# ExternalMotorControllerRev4.net
KiCad netlist of a schematic drawn in EAGLE
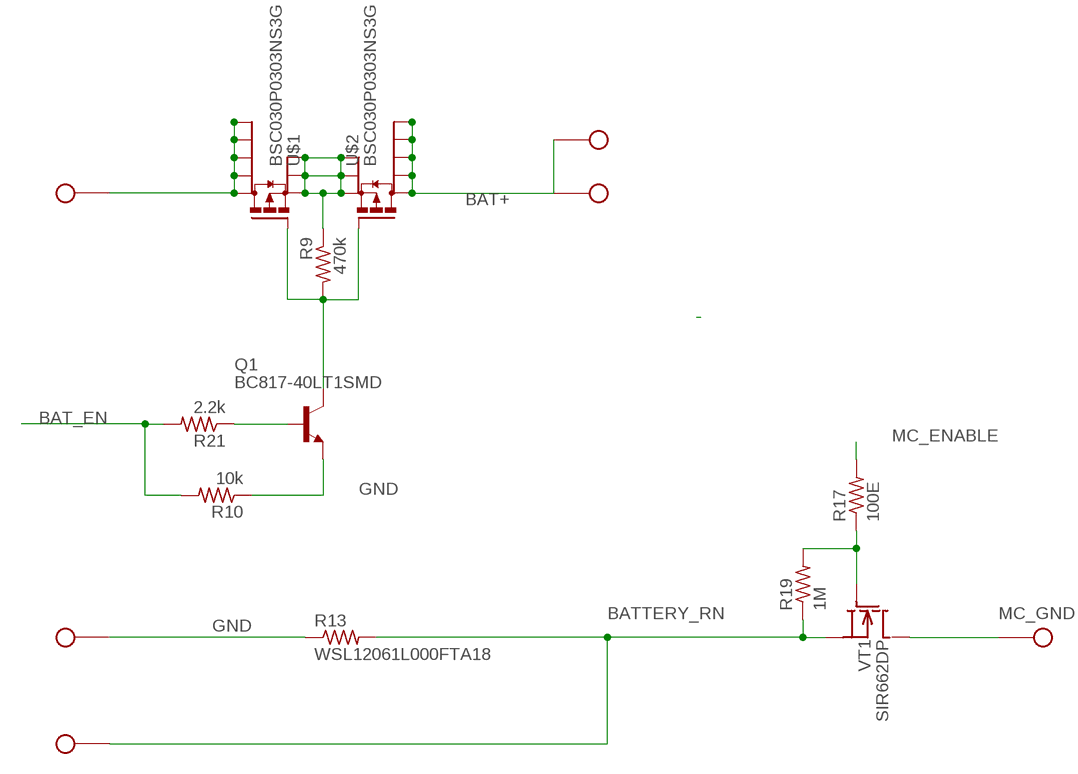
[diagram p0: schematic, sheet 1]
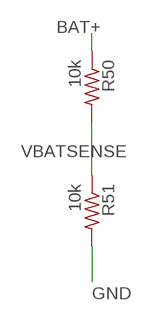
[diagram p1: schematic, sheet 3]
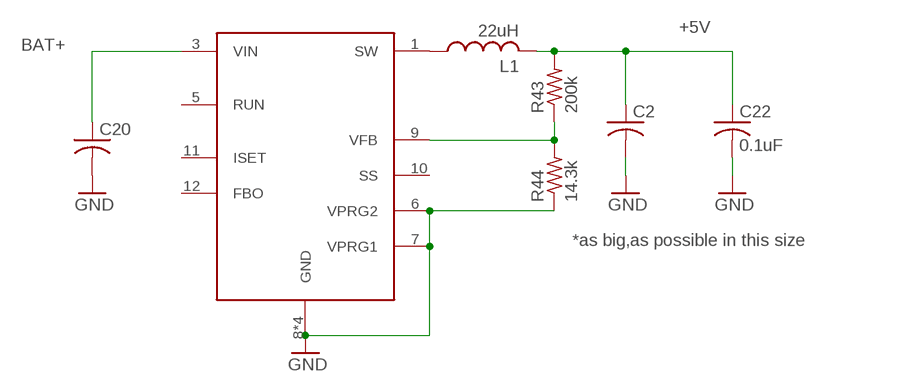
[diagram p2: schematic, sheet 4]
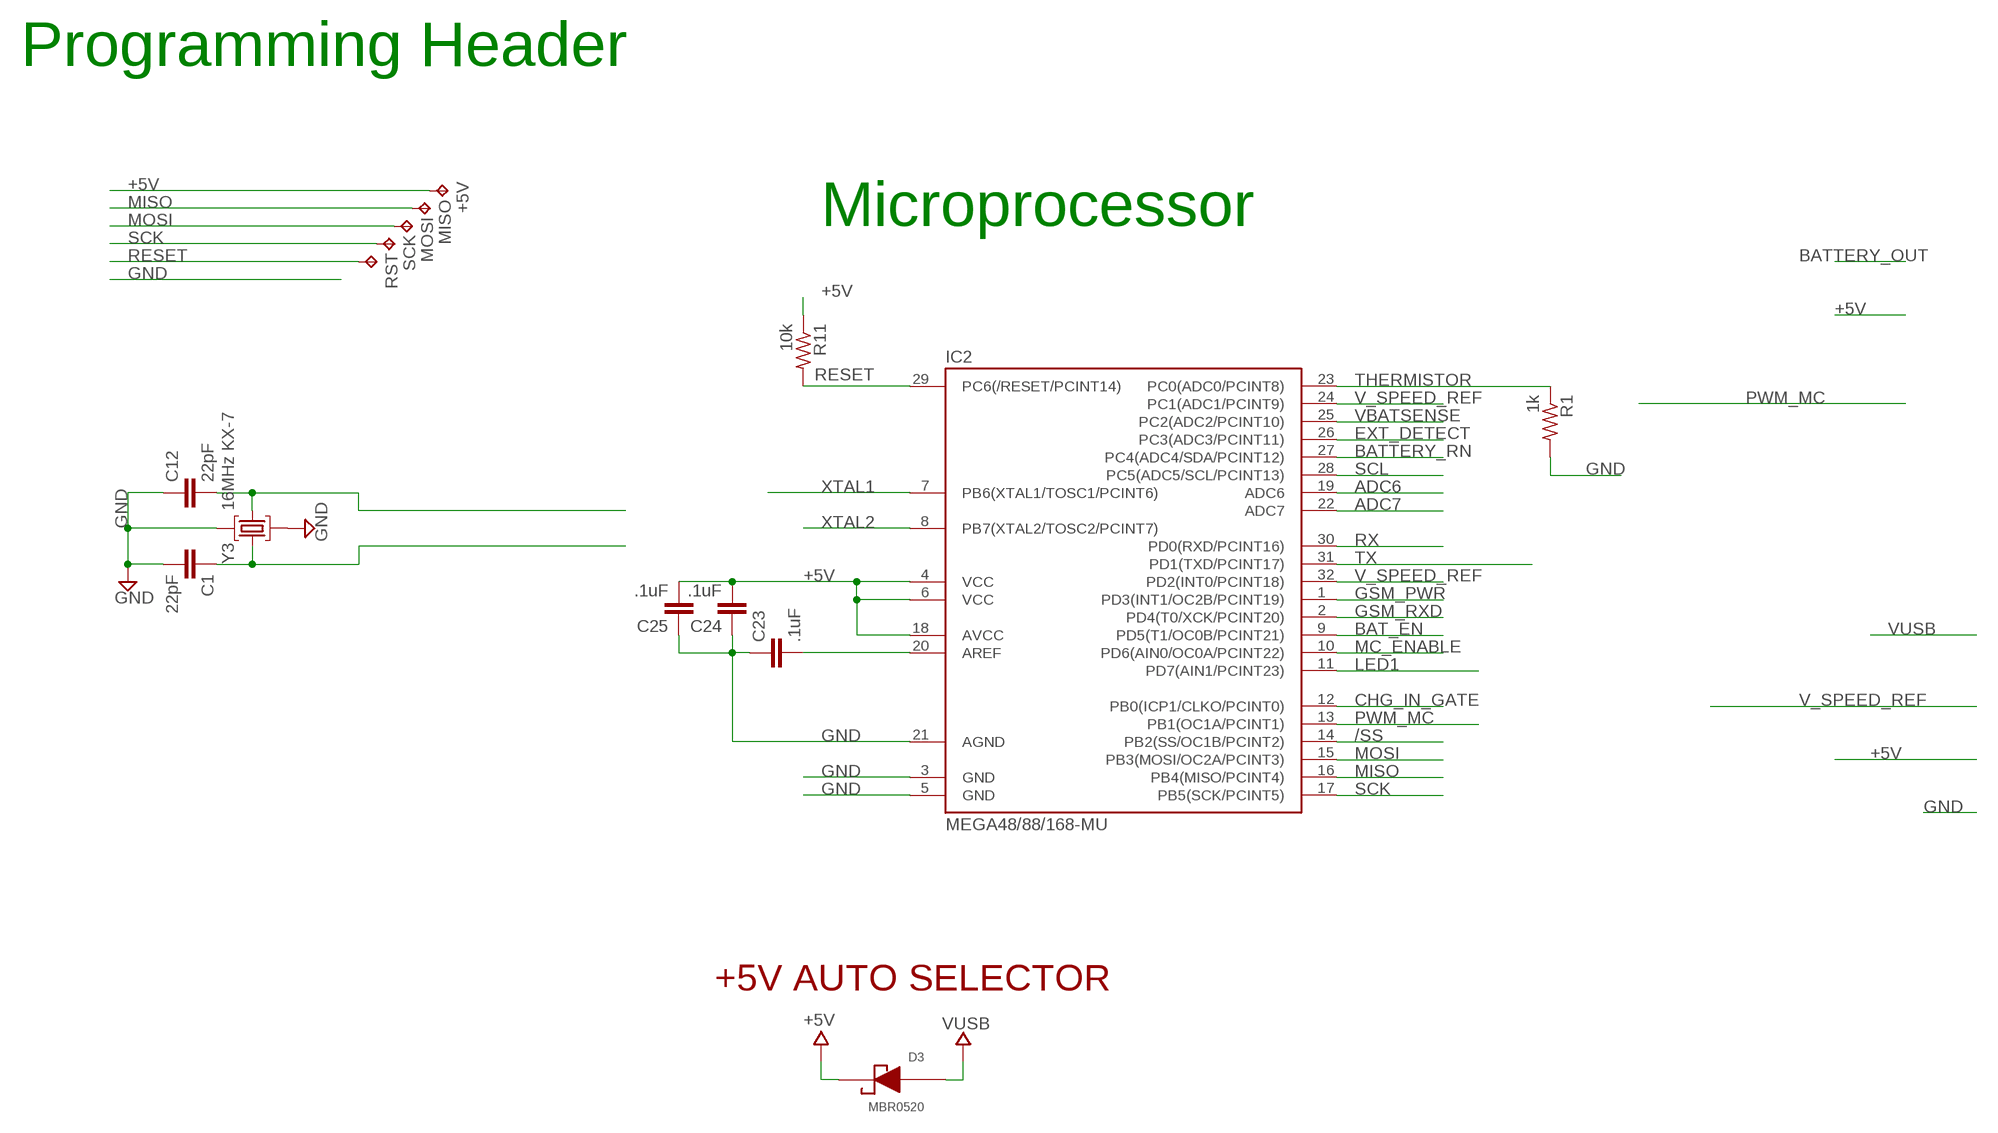
[diagram p3: schematic, sheet 7]

(export (version "E")
  (design (tool "Eeschema 10.0.6"))
  (components
    (comp (ref "Q1")
      (value "BC817-40LT1SMD")
      (footprint "eagle-import:SOT23-BEC")
      (libsource (lib "eagle-import") (part "BC817SMD-40LT1"))
    )
    (comp (ref "R9")
      (value "470k")
      (footprint "eagle-import:R0402")
      (libsource (lib "eagle-import") (part "R-US_R0402"))
    )
    (comp (ref "R10")
      (value "10k")
      (footprint "eagle-import:R0402")
      (libsource (lib "eagle-import") (part "R-US_R0402"))
    )
    (comp (ref "R13")
      (value "WSL12061L000FTA18")
      (footprint "eagle-import:R2512")
      (libsource (lib "eagle-import") (part "R-US_R2512"))
    )
    (comp (ref "R17")
      (value "100E")
      (footprint "eagle-import:R0402")
      (libsource (lib "eagle-import") (part "R-US_R0402"))
    )
    (comp (ref "R19")
      (value "1M")
      (footprint "eagle-import:R0402")
      (libsource (lib "eagle-import") (part "R-US_R0402"))
    )
    (comp (ref "R21")
      (value "2.2k")
      (footprint "eagle-import:R0402")
      (libsource (lib "eagle-import") (part "R-US_R0402"))
    )
    (comp (ref "U$1")
      (value "BSC030P0303NS3G")
      (footprint "eagle-import:PG-TDSON-8")
      (libsource (lib "eagle-import") (part "BSC030P0303NS3G"))
    )
    (comp (ref "U$2")
      (value "BSC030P0303NS3G")
      (footprint "eagle-import:PG-TDSON-8")
      (libsource (lib "eagle-import") (part "BSC030P0303NS3G"))
    )
    (comp (ref "VT1")
      (value "SIR662DP")
      (footprint "eagle-import:POWERPAK_SO8")
      (libsource (lib "eagle-import") (part "SIR662DP"))
    )
    (comp (ref "X1")
      (value "SOLDER_HOLE18AWG")
      (footprint "eagle-import:SOLDER_HOLE_18")
      (libsource (lib "eagle-import") (part "SOLDER_HOLE18AWG"))
    )
    (comp (ref "X2")
      (value "SOLDER_HOLE18AWG")
      (footprint "eagle-import:SOLDER_HOLE_18")
      (libsource (lib "eagle-import") (part "SOLDER_HOLE18AWG"))
    )
    (comp (ref "X3")
      (value "SOLDER_HOLE18AWG")
      (footprint "eagle-import:SOLDER_HOLE_18")
      (libsource (lib "eagle-import") (part "SOLDER_HOLE18AWG"))
    )
    (comp (ref "X4")
      (value "SOLDER_HOLE18AWG")
      (footprint "eagle-import:SOLDER_HOLE_18")
      (libsource (lib "eagle-import") (part "SOLDER_HOLE18AWG"))
    )
    (comp (ref "X5")
      (value "SOLDER_HOLE18AWG")
      (footprint "eagle-import:SOLDER_HOLE_18")
      (libsource (lib "eagle-import") (part "SOLDER_HOLE18AWG"))
    )
    (comp (ref "X13")
      (value "SOLDER_HOLE18AWG")
      (footprint "eagle-import:SOLDER_HOLE_18")
      (libsource (lib "eagle-import") (part "SOLDER_HOLE18AWG"))
    )
    (comp (ref "+5V")
      (value "TPTP08R")
      (footprint "eagle-import:TP08R")
      (libsource (lib "eagle-import") (part "TPTP08R"))
    )
    (comp (ref "C1")
      (value "22pF")
      (footprint "eagle-import:C0402")
      (libsource (lib "eagle-import") (part "rcl_C-EUC0402"))
    )
    (comp (ref "C12")
      (value "22pF")
      (footprint "eagle-import:C0402")
      (libsource (lib "eagle-import") (part "C-EUC0402"))
    )
    (comp (ref "C23")
      (value ".1uF")
      (footprint "eagle-import:C0402")
      (libsource (lib "eagle-import") (part "rcl_C-EUC0402"))
    )
    (comp (ref "C24")
      (value ".1uF")
      (footprint "eagle-import:C0402")
      (libsource (lib "eagle-import") (part "rcl_C-EUC0402"))
    )
    (comp (ref "C25")
      (value ".1uF")
      (footprint "eagle-import:C0402")
      (libsource (lib "eagle-import") (part "rcl_C-EUC0402"))
    )
    (comp (ref "D3")
      (value "MBR0520")
      (footprint "eagle-import:SOD-123")
      (libsource (lib "eagle-import") (part "MBR0520"))
    )
    (comp (ref "IC2")
      (value "MEGA48/88/168-MU")
      (footprint "eagle-import:MLF32")
      (libsource (lib "eagle-import") (part "MEGA48/88/168-MU"))
    )
    (comp (ref "MISO")
      (value "TPTP08R")
      (footprint "eagle-import:TP08R")
      (libsource (lib "eagle-import") (part "TPTP08R"))
    )
    (comp (ref "MOSI")
      (value "TPTP08R")
      (footprint "eagle-import:TP08R")
      (libsource (lib "eagle-import") (part "TPTP08R"))
    )
    (comp (ref "R1")
      (value "1k")
      (footprint "eagle-import:R0402")
      (libsource (lib "eagle-import") (part "rcl_R-US_R0402"))
    )
    (comp (ref "R11")
      (value "10k")
      (footprint "eagle-import:R0402")
      (libsource (lib "eagle-import") (part "rcl_R-US_R0402"))
    )
    (comp (ref "RST")
      (value "TPTP10R")
      (footprint "eagle-import:TP10R")
      (libsource (lib "eagle-import") (part "TPTP10R"))
    )
    (comp (ref "SCK")
      (value "TPTP08R")
      (footprint "eagle-import:TP08R")
      (libsource (lib "eagle-import") (part "TPTP08R"))
    )
    (comp (ref "Y3")
      (value "16MHz KX-7")
      (footprint "eagle-import:CRYSTAL-3.2-2.5")
      (libsource (lib "eagle-import") (part "CRYSTAL-3.2-2.5"))
    )
    (comp (ref "C2")
      (value "C-US")
      (footprint "eagle-import:C2413")
      (libsource (lib "eagle-import") (part "C-US"))
    )
    (comp (ref "C20")
      (value "RCL_C-USC0805")
      (footprint "eagle-import:RCL_C0805$1")
      (libsource (lib "eagle-import") (part "RCL_C-USC0805"))
    )
    (comp (ref "C22")
      (value "0.1uF")
      (footprint "eagle-import:C0402")
      (libsource (lib "eagle-import") (part "C-USC0402"))
    )
    (comp (ref "DA2")
      (value "LTC3630")
      (footprint "eagle-import:MSE16(12)")
      (libsource (lib "eagle-import") (part "LTC3630"))
    )
    (comp (ref "L1")
      (value "22uH")
      (footprint "eagle-import:M-PAD-2.1_1210")
      (libsource (lib "eagle-import") (part "M-PAD-2.1_L_USD"))
    )
    (comp (ref "R43")
      (value "200k")
      (footprint "eagle-import:RCL_R0402")
      (libsource (lib "eagle-import") (part "RCL_R-US_R0402"))
    )
    (comp (ref "R44")
      (value "14.3k")
      (footprint "eagle-import:RCL_R0402")
      (libsource (lib "eagle-import") (part "RCL_R-US_R0402"))
    )
    (comp (ref "R50")
      (value "10k")
      (footprint "eagle-import:R0402")
      (libsource (lib "eagle-import") (part "rcl_R-US_R0402"))
    )
    (comp (ref "R51")
      (value "10k")
      (footprint "eagle-import:R0402")
      (libsource (lib "eagle-import") (part "rcl_R-US_R0402"))
    )
  )
  (nets
    (net (code "1") (name "+5V") (class "Default")
      (node (ref "+5V") (pin "TP") (pinfunction "TP_TP") (pintype "input"))
      (node (ref "C2") (pin "1") (pinfunction "1_1") (pintype "passive"))
      (node (ref "C22") (pin "1") (pinfunction "1_1") (pintype "passive"))
      (node (ref "C24") (pin "2") (pinfunction "2_2") (pintype "passive"))
      (node (ref "C25") (pin "2") (pinfunction "2_2") (pintype "passive"))
      (node (ref "D3") (pin "1") (pinfunction "CA_1") (pintype "passive"))
      (node (ref "IC2") (pin "18") (pinfunction "AVCC_18") (pintype "passive"))
      (node (ref "IC2") (pin "4") (pinfunction "VCC_4") (pintype "power_in"))
      (node (ref "IC2") (pin "6") (pinfunction "VCC_6") (pintype "power_in"))
      (node (ref "L1") (pin "2") (pinfunction "2_2") (pintype "passive"))
      (node (ref "R11") (pin "1") (pinfunction "1_1") (pintype "passive"))
      (node (ref "R43") (pin "2") (pinfunction "2_2") (pintype "passive"))
    )
    (net (code "2") (name "ADC6") (class "Default")
      (node (ref "IC2") (pin "19") (pinfunction "ADC6_19") (pintype "passive"))
    )
    (net (code "3") (name "ADC7") (class "Default")
      (node (ref "IC2") (pin "22") (pinfunction "ADC7_22") (pintype "passive"))
    )
    (net (code "4") (name "BAT+") (class "Default")
      (node (ref "C20") (pin "1") (pinfunction "1_1") (pintype "passive"))
      (node (ref "DA2") (pin "3") (pinfunction "VIN_3") (pintype "power_in"))
      (node (ref "R50") (pin "1") (pinfunction "1_1") (pintype "passive"))
      (node (ref "U$2") (pin "5") (pinfunction "D_5") (pintype "passive"))
      (node (ref "U$2") (pin "6") (pinfunction "D1_6") (pintype "passive"))
      (node (ref "U$2") (pin "7") (pinfunction "D2_7") (pintype "passive"))
      (node (ref "U$2") (pin "8") (pinfunction "D3_8") (pintype "passive"))
      (node (ref "U$2") (pin "TH") (pinfunction "D4_TH") (pintype "passive"))
      (node (ref "X1") (pin "1") (pinfunction "P$1_1") (pintype "bidirectional"))
      (node (ref "X4") (pin "1") (pinfunction "P$1_1") (pintype "bidirectional"))
    )
    (net (code "6") (name "BATTERY_RN") (class "Default")
      (node (ref "IC2") (pin "27") (pinfunction "PC4(ADC4/SDA/PCINT12)_27") (pintype "bidirectional"))
      (node (ref "R13") (pin "2") (pinfunction "2_2") (pintype "passive"))
      (node (ref "R19") (pin "1") (pinfunction "1_1") (pintype "passive"))
      (node (ref "VT1") (pin "S1") (pinfunction "S_S1") (pintype "bidirectional"))
      (node (ref "VT1") (pin "S2") (pinfunction "S_S2") (pintype "bidirectional"))
      (node (ref "VT1") (pin "S3") (pinfunction "S_S3") (pintype "bidirectional"))
      (node (ref "X3") (pin "1") (pinfunction "P$1_1") (pintype "bidirectional"))
    )
    (net (code "7") (name "BAT_EN") (class "Default")
      (node (ref "IC2") (pin "9") (pinfunction "PD5(T1/OC0B/PCINT21)_9") (pintype "bidirectional"))
      (node (ref "R10") (pin "2") (pinfunction "2_2") (pintype "passive"))
      (node (ref "R21") (pin "2") (pinfunction "2_2") (pintype "passive"))
    )
    (net (code "8") (name "CHG_IN_GATE") (class "Default")
      (node (ref "IC2") (pin "12") (pinfunction "PB0(ICP1/CLKO/PCINT0)_12") (pintype "bidirectional"))
    )
    (net (code "9") (name "EXT_DETECT") (class "Default")
      (node (ref "IC2") (pin "26") (pinfunction "PC3(ADC3/PCINT11)_26") (pintype "bidirectional"))
    )
    (net (code "10") (name "GND") (class "Default")
      (node (ref "C1") (pin "2") (pinfunction "2_2") (pintype "passive"))
      (node (ref "C12") (pin "1") (pinfunction "1_1") (pintype "passive"))
      (node (ref "C2") (pin "2") (pinfunction "2_2") (pintype "passive"))
      (node (ref "C20") (pin "2") (pinfunction "2_2") (pintype "passive"))
      (node (ref "C22") (pin "2") (pinfunction "2_2") (pintype "passive"))
      (node (ref "C23") (pin "1") (pinfunction "1_1") (pintype "passive"))
      (node (ref "C24") (pin "1") (pinfunction "1_1") (pintype "passive"))
      (node (ref "C25") (pin "1") (pinfunction "1_1") (pintype "passive"))
      (node (ref "DA2") (pin "14") (pinfunction "GND_14") (pintype "bidirectional"))
      (node (ref "DA2") (pin "16") (pinfunction "GND_16") (pintype "bidirectional"))
      (node (ref "DA2") (pin "17") (pinfunction "GND_17") (pintype "bidirectional"))
      (node (ref "DA2") (pin "6") (pinfunction "VPRG2_6") (pintype "input"))
      (node (ref "DA2") (pin "7") (pinfunction "VPRG1_7") (pintype "input"))
      (node (ref "DA2") (pin "8") (pinfunction "GND_8") (pintype "bidirectional"))
      (node (ref "IC2") (pin "21") (pinfunction "AGND_21") (pintype "power_in"))
      (node (ref "IC2") (pin "3") (pinfunction "GND_3") (pintype "power_in"))
      (node (ref "IC2") (pin "5") (pinfunction "GND_5") (pintype "power_in"))
      (node (ref "Q1") (pin "E") (pinfunction "E_E") (pintype "passive"))
      (node (ref "R1") (pin "2") (pinfunction "2_2") (pintype "passive"))
      (node (ref "R10") (pin "1") (pinfunction "1_1") (pintype "passive"))
      (node (ref "R13") (pin "1") (pinfunction "1_1") (pintype "passive"))
      (node (ref "R44") (pin "1") (pinfunction "1_1") (pintype "passive"))
      (node (ref "R51") (pin "2") (pinfunction "2_2") (pintype "passive"))
      (node (ref "X13") (pin "1") (pinfunction "P$1_1") (pintype "bidirectional"))
      (node (ref "Y3") (pin "2") (pinfunction "GND_2") (pintype "passive"))
      (node (ref "Y3") (pin "4") (pinfunction "GND_4") (pintype "passive"))
    )
    (net (code "11") (name "GSM_PWR") (class "Default")
      (node (ref "IC2") (pin "1") (pinfunction "PD3(INT1/OC2B/PCINT19)_1") (pintype "bidirectional"))
    )
    (net (code "12") (name "GSM_RXD") (class "Default")
      (node (ref "IC2") (pin "2") (pinfunction "PD4(T0/XCK/PCINT20)_2") (pintype "bidirectional"))
    )
    (net (code "13") (name "LED1") (class "Default")
      (node (ref "IC2") (pin "11") (pinfunction "PD7(AIN1/PCINT23)_11") (pintype "bidirectional"))
    )
    (net (code "14") (name "MC_ENABLE") (class "Default")
      (node (ref "IC2") (pin "10") (pinfunction "PD6(AIN0/OC0A/PCINT22)_10") (pintype "bidirectional"))
      (node (ref "R17") (pin "2") (pinfunction "2_2") (pintype "passive"))
    )
    (net (code "15") (name "MC_GND") (class "Default")
      (node (ref "VT1") (pin "D") (pinfunction "D_D") (pintype "bidirectional"))
      (node (ref "X2") (pin "1") (pinfunction "P$1_1") (pintype "bidirectional"))
    )
    (net (code "16") (name "MISO") (class "Default")
      (node (ref "IC2") (pin "16") (pinfunction "PB4(MISO/PCINT4)_16") (pintype "bidirectional"))
      (node (ref "MISO") (pin "TP") (pinfunction "TP_TP") (pintype "input"))
    )
    (net (code "17") (name "MOSI") (class "Default")
      (node (ref "IC2") (pin "15") (pinfunction "PB3(MOSI/OC2A/PCINT3)_15") (pintype "bidirectional"))
      (node (ref "MOSI") (pin "TP") (pinfunction "TP_TP") (pintype "input"))
    )
    (net (code "18") (name "Net-(DA2-SW)") (class "Default")
      (node (ref "DA2") (pin "1") (pinfunction "SW_1") (pintype "power_in"))
      (node (ref "L1") (pin "1") (pinfunction "1_1") (pintype "passive"))
    )
    (net (code "19") (name "Net-(DA2-VFB)") (class "Default")
      (node (ref "DA2") (pin "9") (pinfunction "VFB_9") (pintype "input"))
      (node (ref "R43") (pin "1") (pinfunction "1_1") (pintype "passive"))
      (node (ref "R44") (pin "2") (pinfunction "2_2") (pintype "passive"))
    )
    (net (code "20") (name "Net-(IC2-AREF)") (class "Default")
      (node (ref "C23") (pin "2") (pinfunction "2_2") (pintype "passive"))
      (node (ref "IC2") (pin "20") (pinfunction "AREF_20") (pintype "passive"))
    )
    (net (code "21") (name "Net-(Q1-PadB)") (class "Default")
      (node (ref "Q1") (pin "B") (pinfunction "B_B") (pintype "passive"))
      (node (ref "R21") (pin "1") (pinfunction "1_1") (pintype "passive"))
    )
    (net (code "22") (name "Net-(R17-Pad1)") (class "Default")
      (node (ref "R17") (pin "1") (pinfunction "1_1") (pintype "passive"))
      (node (ref "R19") (pin "2") (pinfunction "2_2") (pintype "passive"))
      (node (ref "VT1") (pin "G") (pinfunction "G_G") (pintype "bidirectional"))
    )
    (net (code "23") (name "Net-(U$1-D)") (class "Default")
      (node (ref "U$1") (pin "5") (pinfunction "D_5") (pintype "passive"))
      (node (ref "U$1") (pin "6") (pinfunction "D1_6") (pintype "passive"))
      (node (ref "U$1") (pin "7") (pinfunction "D2_7") (pintype "passive"))
      (node (ref "U$1") (pin "8") (pinfunction "D3_8") (pintype "passive"))
      (node (ref "U$1") (pin "TH") (pinfunction "D4_TH") (pintype "passive"))
      (node (ref "X5") (pin "1") (pinfunction "P$1_1") (pintype "bidirectional"))
    )
    (net (code "24") (name "Net-(U$1-G)") (class "Default")
      (node (ref "Q1") (pin "C") (pinfunction "C_C") (pintype "passive"))
      (node (ref "R9") (pin "2") (pinfunction "2_2") (pintype "passive"))
      (node (ref "U$1") (pin "4") (pinfunction "G_4") (pintype "passive"))
      (node (ref "U$2") (pin "4") (pinfunction "G_4") (pintype "passive"))
    )
    (net (code "25") (name "Net-(U$1-S)") (class "Default")
      (node (ref "R9") (pin "1") (pinfunction "1_1") (pintype "passive"))
      (node (ref "U$1") (pin "1") (pinfunction "S_1") (pintype "passive"))
      (node (ref "U$1") (pin "2") (pinfunction "S1_2") (pintype "passive"))
      (node (ref "U$1") (pin "3") (pinfunction "S2_3") (pintype "passive"))
      (node (ref "U$2") (pin "1") (pinfunction "S_1") (pintype "passive"))
      (node (ref "U$2") (pin "2") (pinfunction "S1_2") (pintype "passive"))
      (node (ref "U$2") (pin "3") (pinfunction "S2_3") (pintype "passive"))
    )
    (net (code "26") (name "PWM_MC") (class "Default")
      (node (ref "IC2") (pin "13") (pinfunction "PB1(OC1A/PCINT1)_13") (pintype "bidirectional"))
    )
    (net (code "27") (name "RESET") (class "Default")
      (node (ref "IC2") (pin "29") (pinfunction "PC6(/RESET/PCINT14)_29") (pintype "bidirectional"))
      (node (ref "R11") (pin "2") (pinfunction "2_2") (pintype "passive"))
      (node (ref "RST") (pin "TP") (pinfunction "TP_TP") (pintype "input"))
    )
    (net (code "28") (name "RX") (class "Default")
      (node (ref "IC2") (pin "30") (pinfunction "PD0(RXD/PCINT16)_30") (pintype "bidirectional"))
    )
    (net (code "29") (name "SCK") (class "Default")
      (node (ref "IC2") (pin "17") (pinfunction "PB5(SCK/PCINT5)_17") (pintype "bidirectional"))
      (node (ref "SCK") (pin "TP") (pinfunction "TP_TP") (pintype "input"))
    )
    (net (code "30") (name "SCL") (class "Default")
      (node (ref "IC2") (pin "28") (pinfunction "PC5(ADC5/SCL/PCINT13)_28") (pintype "bidirectional"))
    )
    (net (code "31") (name "THERMISTOR") (class "Default")
      (node (ref "IC2") (pin "23") (pinfunction "PC0(ADC0/PCINT8)_23") (pintype "bidirectional"))
      (node (ref "R1") (pin "1") (pinfunction "1_1") (pintype "passive"))
    )
    (net (code "32") (name "TX") (class "Default")
      (node (ref "IC2") (pin "31") (pinfunction "PD1(TXD/PCINT17)_31") (pintype "bidirectional"))
    )
    (net (code "33") (name "VBATSENSE") (class "Default")
      (node (ref "IC2") (pin "25") (pinfunction "PC2(ADC2/PCINT10)_25") (pintype "bidirectional"))
      (node (ref "R50") (pin "2") (pinfunction "2_2") (pintype "passive"))
      (node (ref "R51") (pin "1") (pinfunction "1_1") (pintype "passive"))
    )
    (net (code "34") (name "VUSB") (class "Default")
      (node (ref "D3") (pin "2") (pinfunction "AN_2") (pintype "passive"))
    )
    (net (code "35") (name "V_SPEED_REF") (class "Default")
      (node (ref "IC2") (pin "24") (pinfunction "PC1(ADC1/PCINT9)_24") (pintype "bidirectional"))
      (node (ref "IC2") (pin "32") (pinfunction "PD2(INT0/PCINT18)_32") (pintype "bidirectional"))
    )
    (net (code "36") (name "XTAL1") (class "Default")
      (node (ref "C1") (pin "1") (pinfunction "1_1") (pintype "passive"))
      (node (ref "IC2") (pin "7") (pinfunction "PB6(XTAL1/TOSC1/PCINT6)_7") (pintype "bidirectional"))
      (node (ref "Y3") (pin "3") (pinfunction "C2_3") (pintype "passive"))
    )
    (net (code "37") (name "XTAL2") (class "Default")
      (node (ref "C12") (pin "2") (pinfunction "2_2") (pintype "passive"))
      (node (ref "IC2") (pin "8") (pinfunction "PB7(XTAL2/TOSC2/PCINT7)_8") (pintype "bidirectional"))
      (node (ref "Y3") (pin "1") (pinfunction "C1_1") (pintype "passive"))
    )
    (net (code "38") (name "unconnected-(DA2-FBO-Pad12)") (class "Default")
      (node (ref "DA2") (pin "12") (pinfunction "FBO_12") (pintype "input"))
    )
    (net (code "39") (name "unconnected-(DA2-ISET-Pad11)") (class "Default")
      (node (ref "DA2") (pin "11") (pinfunction "ISET_11") (pintype "input"))
    )
    (net (code "40") (name "unconnected-(DA2-RUN-Pad5)") (class "Default")
      (node (ref "DA2") (pin "5") (pinfunction "RUN_5") (pintype "input"))
    )
    (net (code "41") (name "unconnected-(DA2-SS-Pad10)") (class "Default")
      (node (ref "DA2") (pin "10") (pinfunction "SS_10") (pintype "input"))
    )
    (net (code "42") (name "{slash}SS") (class "Default")
      (node (ref "IC2") (pin "14") (pinfunction "PB2(SS/OC1B/PCINT2)_14") (pintype "bidirectional"))
    )
  )
)
